# Schem_task_10_1.net
KiCad netlist of a schematic drawn in EasyEDA
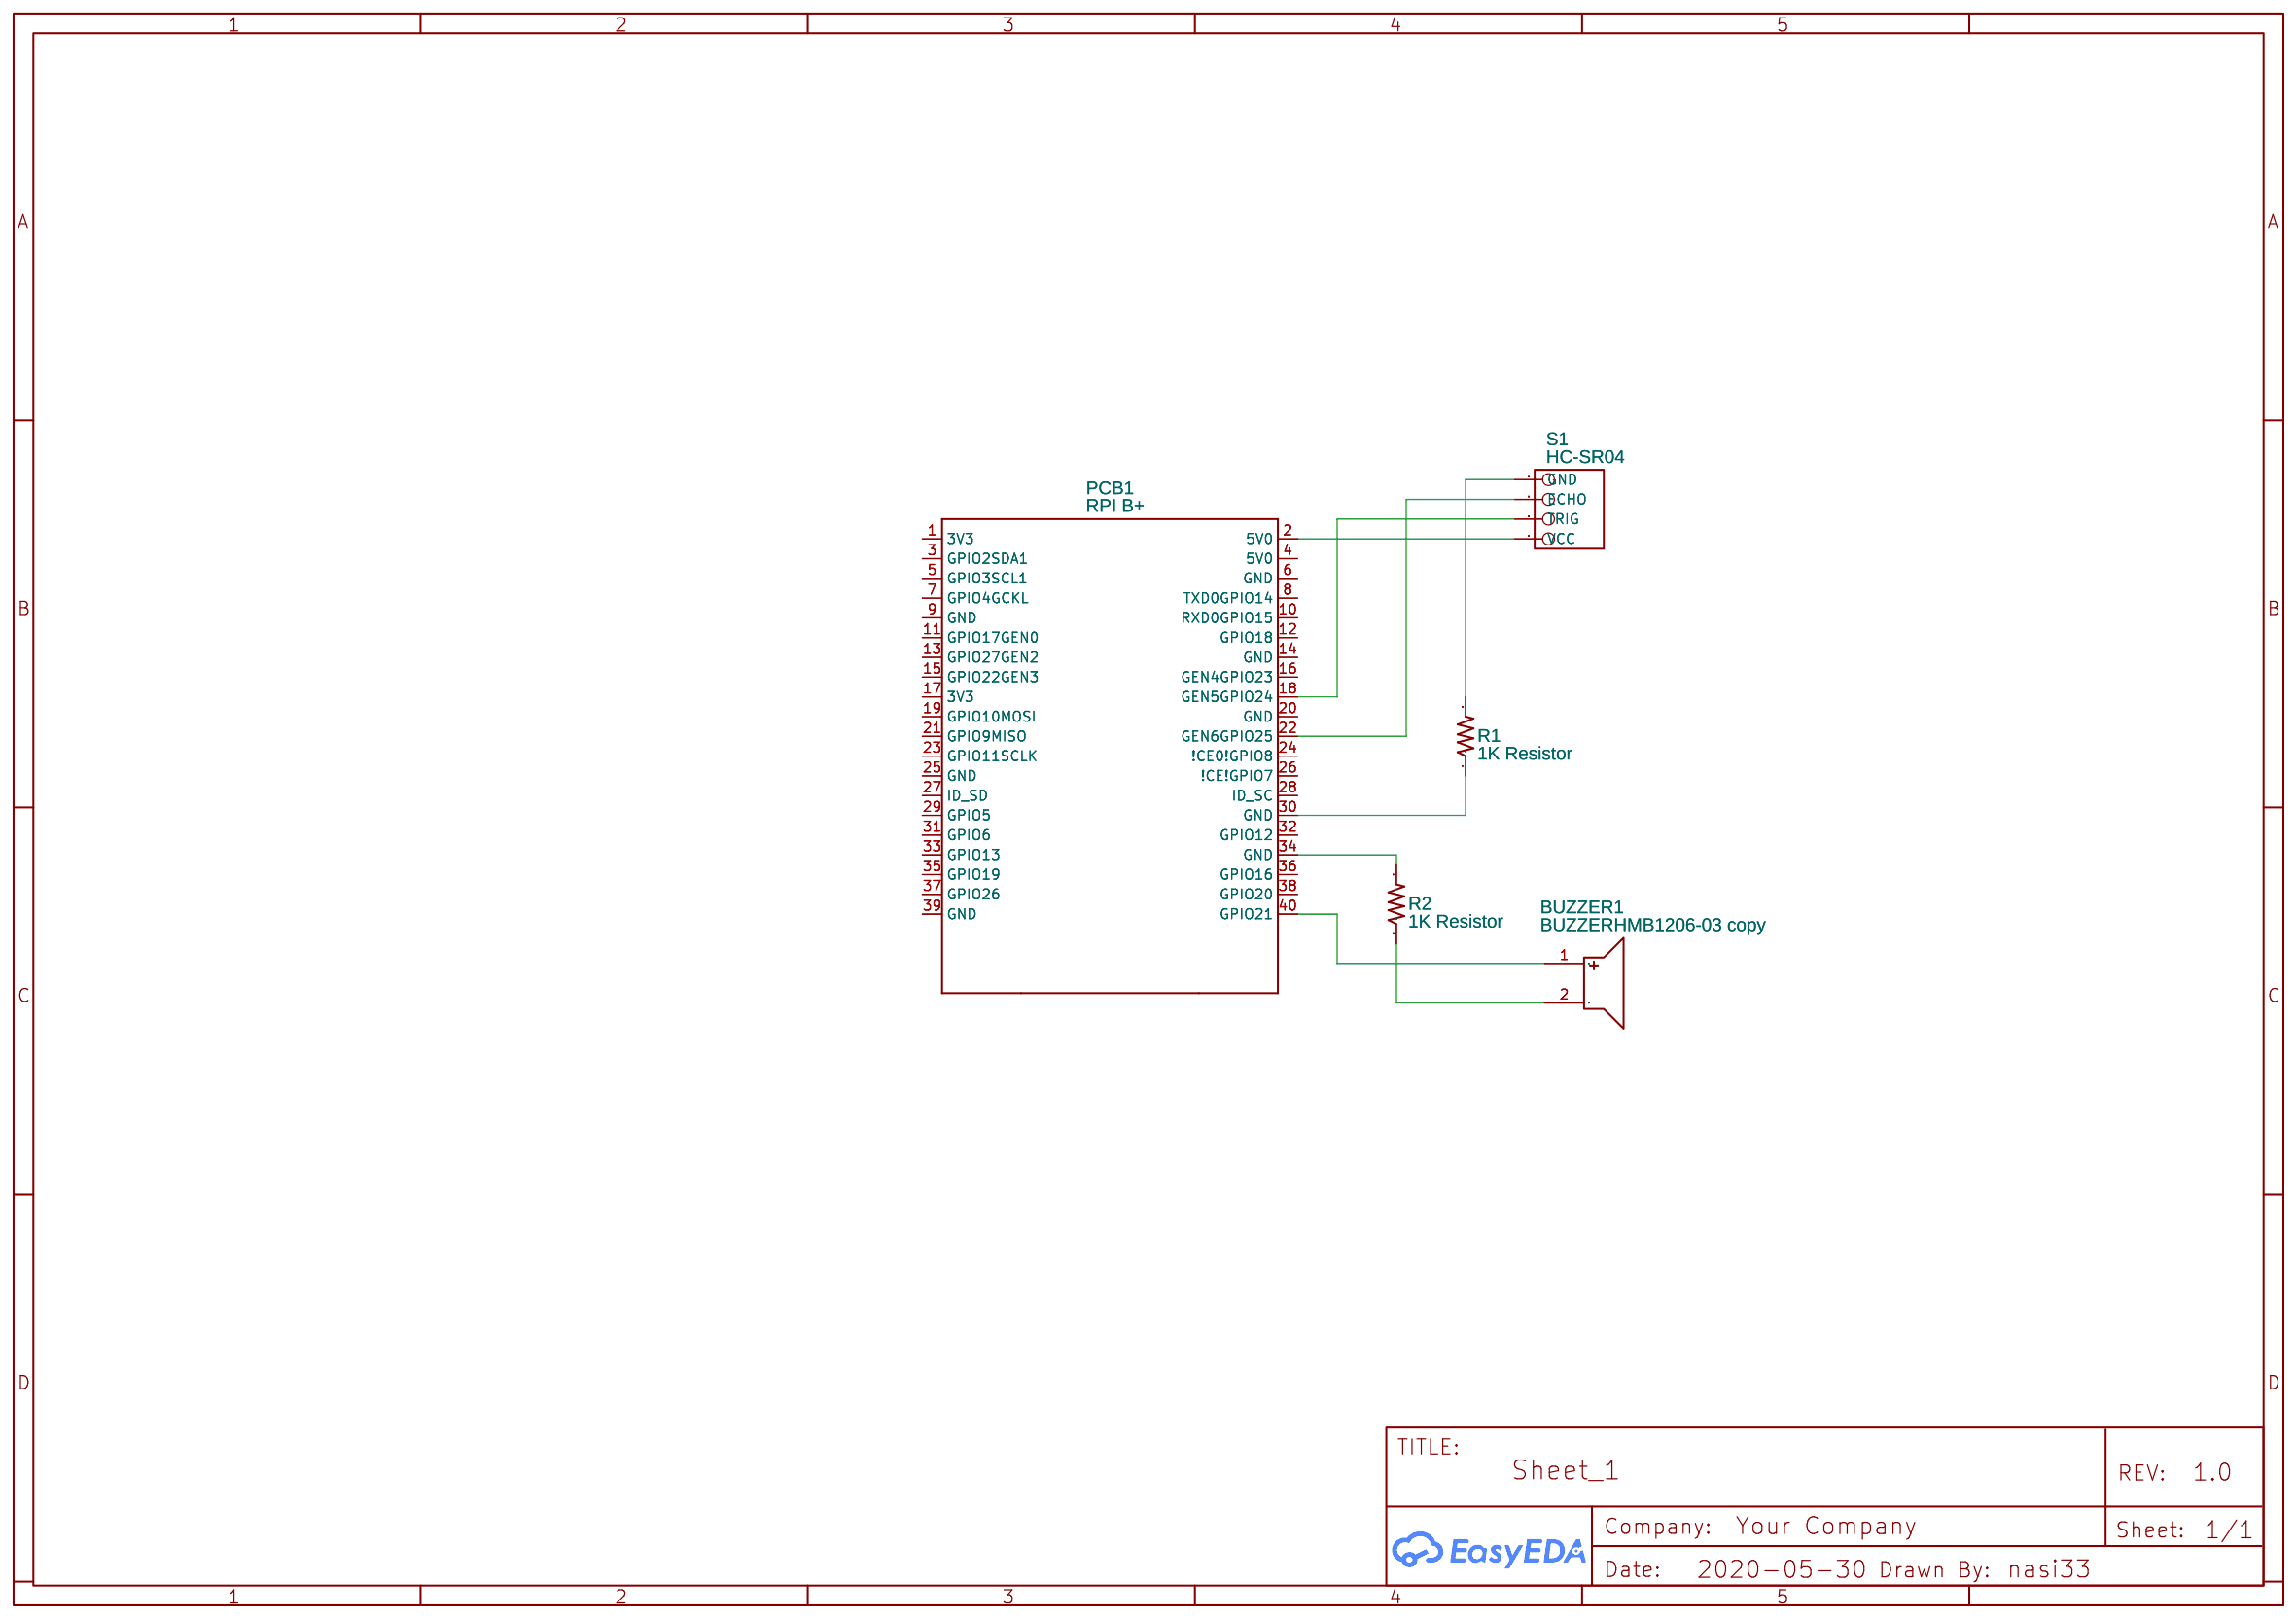
[diagram p0: schematic sheet]

(export (version "E")
  (design (tool "Eeschema 10.0.6"))
  (components
    (comp (ref "BUZZER1")
      (value "BUZZERHMB1206-03 copy")
      (fields
        (field (name "BOM_Manufacturer Part") "BUZZERHMB1206-03")
        (field (name "BOM_Supplier Part") "C96101")
      )
      (libsource (lib "") (part "BUZZERHMB1206-03 copy"))
    )
    (comp (ref "PCB1") (value "RPI B+") (libsource (lib "") (part "RPI B+")))
    (comp (ref "R1") (value "1K Resistor") (libsource (lib "") (part "1K Resistor")))
    (comp (ref "R2") (value "1K Resistor") (libsource (lib "") (part "1K Resistor")))
    (comp (ref "S1") (value "HC-SR04") (libsource (lib "") (part "HC-SR04")))
  )
  (nets
    (net (code "1") (name "Net-(BUZZER1-Pad2)") (class "Default")
      (node (ref "BUZZER1") (pin "2") (pinfunction "2_2") (pintype "unspecified"))
      (node (ref "R2") (pin "1") (pinfunction "1_1") (pintype "unspecified"))
    )
    (net (code "2") (name "Net-(PCB1-GEN5GPIO24)") (class "Default")
      (node (ref "PCB1") (pin "18") (pinfunction "GEN5GPIO24_18") (pintype "unspecified"))
      (node (ref "S1") (pin "2") (pinfunction "TRIG_2") (pintype "unspecified"))
    )
    (net (code "3") (name "Net-(PCB1-GEN6GPIO25)") (class "Default")
      (node (ref "PCB1") (pin "22") (pinfunction "GEN6GPIO25_22") (pintype "unspecified"))
      (node (ref "S1") (pin "3") (pinfunction "ECHO_3") (pintype "unspecified"))
    )
    (net (code "4") (name "Net-(PCB1-GND-Pad30)") (class "Default")
      (node (ref "PCB1") (pin "30") (pinfunction "GND_30") (pintype "unspecified"))
      (node (ref "R1") (pin "1") (pinfunction "1_1") (pintype "unspecified"))
    )
    (net (code "5") (name "Net-(PCB1-GND-Pad34)") (class "Default")
      (node (ref "PCB1") (pin "34") (pinfunction "GND_34") (pintype "unspecified"))
      (node (ref "R2") (pin "2") (pinfunction "2_2") (pintype "unspecified"))
    )
    (net (code "6") (name "Net-(PCB1-GPIO21)") (class "Default")
      (node (ref "BUZZER1") (pin "1") (pinfunction "1_1") (pintype "unspecified"))
      (node (ref "PCB1") (pin "40") (pinfunction "GPIO21_40") (pintype "unspecified"))
    )
    (net (code "7") (name "Net-(S1-GND)") (class "Default")
      (node (ref "R1") (pin "2") (pinfunction "2_2") (pintype "unspecified"))
      (node (ref "S1") (pin "4") (pinfunction "GND_4") (pintype "unspecified"))
    )
    (net (code "8") (name "Net-(S1-VCC)") (class "Default")
      (node (ref "PCB1") (pin "2") (pinfunction "5V0_2") (pintype "unspecified"))
      (node (ref "S1") (pin "1") (pinfunction "VCC_1") (pintype "unspecified"))
    )
    (net (code "9") (name "unconnected-(PCB1-!CE!GPIO7-Pad26)") (class "Default")
      (node (ref "PCB1") (pin "26") (pinfunction "!CE!GPIO7_26") (pintype "unspecified"))
    )
    (net (code "10") (name "unconnected-(PCB1-!CE0!GPIO8-Pad24)") (class "Default")
      (node (ref "PCB1") (pin "24") (pinfunction "!CE0!GPIO8_24") (pintype "unspecified"))
    )
    (net (code "11") (name "unconnected-(PCB1-3V3-Pad1)") (class "Default")
      (node (ref "PCB1") (pin "1") (pinfunction "3V3_1") (pintype "unspecified"))
    )
    (net (code "12") (name "unconnected-(PCB1-3V3-Pad17)") (class "Default")
      (node (ref "PCB1") (pin "17") (pinfunction "3V3_17") (pintype "unspecified"))
    )
    (net (code "13") (name "unconnected-(PCB1-5V0-Pad4)") (class "Default")
      (node (ref "PCB1") (pin "4") (pinfunction "5V0_4") (pintype "unspecified"))
    )
    (net (code "14") (name "unconnected-(PCB1-GEN4GPIO23-Pad16)") (class "Default")
      (node (ref "PCB1") (pin "16") (pinfunction "GEN4GPIO23_16") (pintype "unspecified"))
    )
    (net (code "15") (name "unconnected-(PCB1-GND-Pad6)") (class "Default")
      (node (ref "PCB1") (pin "6") (pinfunction "GND_6") (pintype "unspecified"))
    )
    (net (code "16") (name "unconnected-(PCB1-GND-Pad9)") (class "Default")
      (node (ref "PCB1") (pin "9") (pinfunction "GND_9") (pintype "unspecified"))
    )
    (net (code "17") (name "unconnected-(PCB1-GND-Pad14)") (class "Default")
      (node (ref "PCB1") (pin "14") (pinfunction "GND_14") (pintype "unspecified"))
    )
    (net (code "18") (name "unconnected-(PCB1-GND-Pad20)") (class "Default")
      (node (ref "PCB1") (pin "20") (pinfunction "GND_20") (pintype "unspecified"))
    )
    (net (code "19") (name "unconnected-(PCB1-GND-Pad25)") (class "Default")
      (node (ref "PCB1") (pin "25") (pinfunction "GND_25") (pintype "unspecified"))
    )
    (net (code "20") (name "unconnected-(PCB1-GND-Pad39)") (class "Default")
      (node (ref "PCB1") (pin "39") (pinfunction "GND_39") (pintype "unspecified"))
    )
    (net (code "21") (name "unconnected-(PCB1-GPIO2SDA1-Pad3)") (class "Default")
      (node (ref "PCB1") (pin "3") (pinfunction "GPIO2SDA1_3") (pintype "unspecified"))
    )
    (net (code "22") (name "unconnected-(PCB1-GPIO3SCL1-Pad5)") (class "Default")
      (node (ref "PCB1") (pin "5") (pinfunction "GPIO3SCL1_5") (pintype "unspecified"))
    )
    (net (code "23") (name "unconnected-(PCB1-GPIO4GCKL-Pad7)") (class "Default")
      (node (ref "PCB1") (pin "7") (pinfunction "GPIO4GCKL_7") (pintype "unspecified"))
    )
    (net (code "24") (name "unconnected-(PCB1-GPIO5-Pad29)") (class "Default")
      (node (ref "PCB1") (pin "29") (pinfunction "GPIO5_29") (pintype "unspecified"))
    )
    (net (code "25") (name "unconnected-(PCB1-GPIO6-Pad31)") (class "Default")
      (node (ref "PCB1") (pin "31") (pinfunction "GPIO6_31") (pintype "unspecified"))
    )
    (net (code "26") (name "unconnected-(PCB1-GPIO9MISO-Pad21)") (class "Default")
      (node (ref "PCB1") (pin "21") (pinfunction "GPIO9MISO_21") (pintype "unspecified"))
    )
    (net (code "27") (name "unconnected-(PCB1-GPIO10MOSI-Pad19)") (class "Default")
      (node (ref "PCB1") (pin "19") (pinfunction "GPIO10MOSI_19") (pintype "unspecified"))
    )
    (net (code "28") (name "unconnected-(PCB1-GPIO11SCLK-Pad23)") (class "Default")
      (node (ref "PCB1") (pin "23") (pinfunction "GPIO11SCLK_23") (pintype "unspecified"))
    )
    (net (code "29") (name "unconnected-(PCB1-GPIO12-Pad32)") (class "Default")
      (node (ref "PCB1") (pin "32") (pinfunction "GPIO12_32") (pintype "unspecified"))
    )
    (net (code "30") (name "unconnected-(PCB1-GPIO13-Pad33)") (class "Default")
      (node (ref "PCB1") (pin "33") (pinfunction "GPIO13_33") (pintype "unspecified"))
    )
    (net (code "31") (name "unconnected-(PCB1-GPIO16-Pad36)") (class "Default")
      (node (ref "PCB1") (pin "36") (pinfunction "GPIO16_36") (pintype "unspecified"))
    )
    (net (code "32") (name "unconnected-(PCB1-GPIO17GEN0-Pad11)") (class "Default")
      (node (ref "PCB1") (pin "11") (pinfunction "GPIO17GEN0_11") (pintype "unspecified"))
    )
    (net (code "33") (name "unconnected-(PCB1-GPIO18-Pad12)") (class "Default")
      (node (ref "PCB1") (pin "12") (pinfunction "GPIO18_12") (pintype "unspecified"))
    )
    (net (code "34") (name "unconnected-(PCB1-GPIO19-Pad35)") (class "Default")
      (node (ref "PCB1") (pin "35") (pinfunction "GPIO19_35") (pintype "unspecified"))
    )
    (net (code "35") (name "unconnected-(PCB1-GPIO20-Pad38)") (class "Default")
      (node (ref "PCB1") (pin "38") (pinfunction "GPIO20_38") (pintype "unspecified"))
    )
    (net (code "36") (name "unconnected-(PCB1-GPIO22GEN3-Pad15)") (class "Default")
      (node (ref "PCB1") (pin "15") (pinfunction "GPIO22GEN3_15") (pintype "unspecified"))
    )
    (net (code "37") (name "unconnected-(PCB1-GPIO26-Pad37)") (class "Default")
      (node (ref "PCB1") (pin "37") (pinfunction "GPIO26_37") (pintype "unspecified"))
    )
    (net (code "38") (name "unconnected-(PCB1-GPIO27GEN2-Pad13)") (class "Default")
      (node (ref "PCB1") (pin "13") (pinfunction "GPIO27GEN2_13") (pintype "unspecified"))
    )
    (net (code "39") (name "unconnected-(PCB1-ID_SC-Pad28)") (class "Default")
      (node (ref "PCB1") (pin "28") (pinfunction "ID_SC_28") (pintype "unspecified"))
    )
    (net (code "40") (name "unconnected-(PCB1-ID_SD-Pad27)") (class "Default")
      (node (ref "PCB1") (pin "27") (pinfunction "ID_SD_27") (pintype "unspecified"))
    )
    (net (code "41") (name "unconnected-(PCB1-RXD0GPIO15-Pad10)") (class "Default")
      (node (ref "PCB1") (pin "10") (pinfunction "RXD0GPIO15_10") (pintype "unspecified"))
    )
    (net (code "42") (name "unconnected-(PCB1-TXD0GPIO14-Pad8)") (class "Default")
      (node (ref "PCB1") (pin "8") (pinfunction "TXD0GPIO14_8") (pintype "unspecified"))
    )
  )
)
